# WL-DAC.net
KiCad netlist of a schematic drawn in Altium Designer
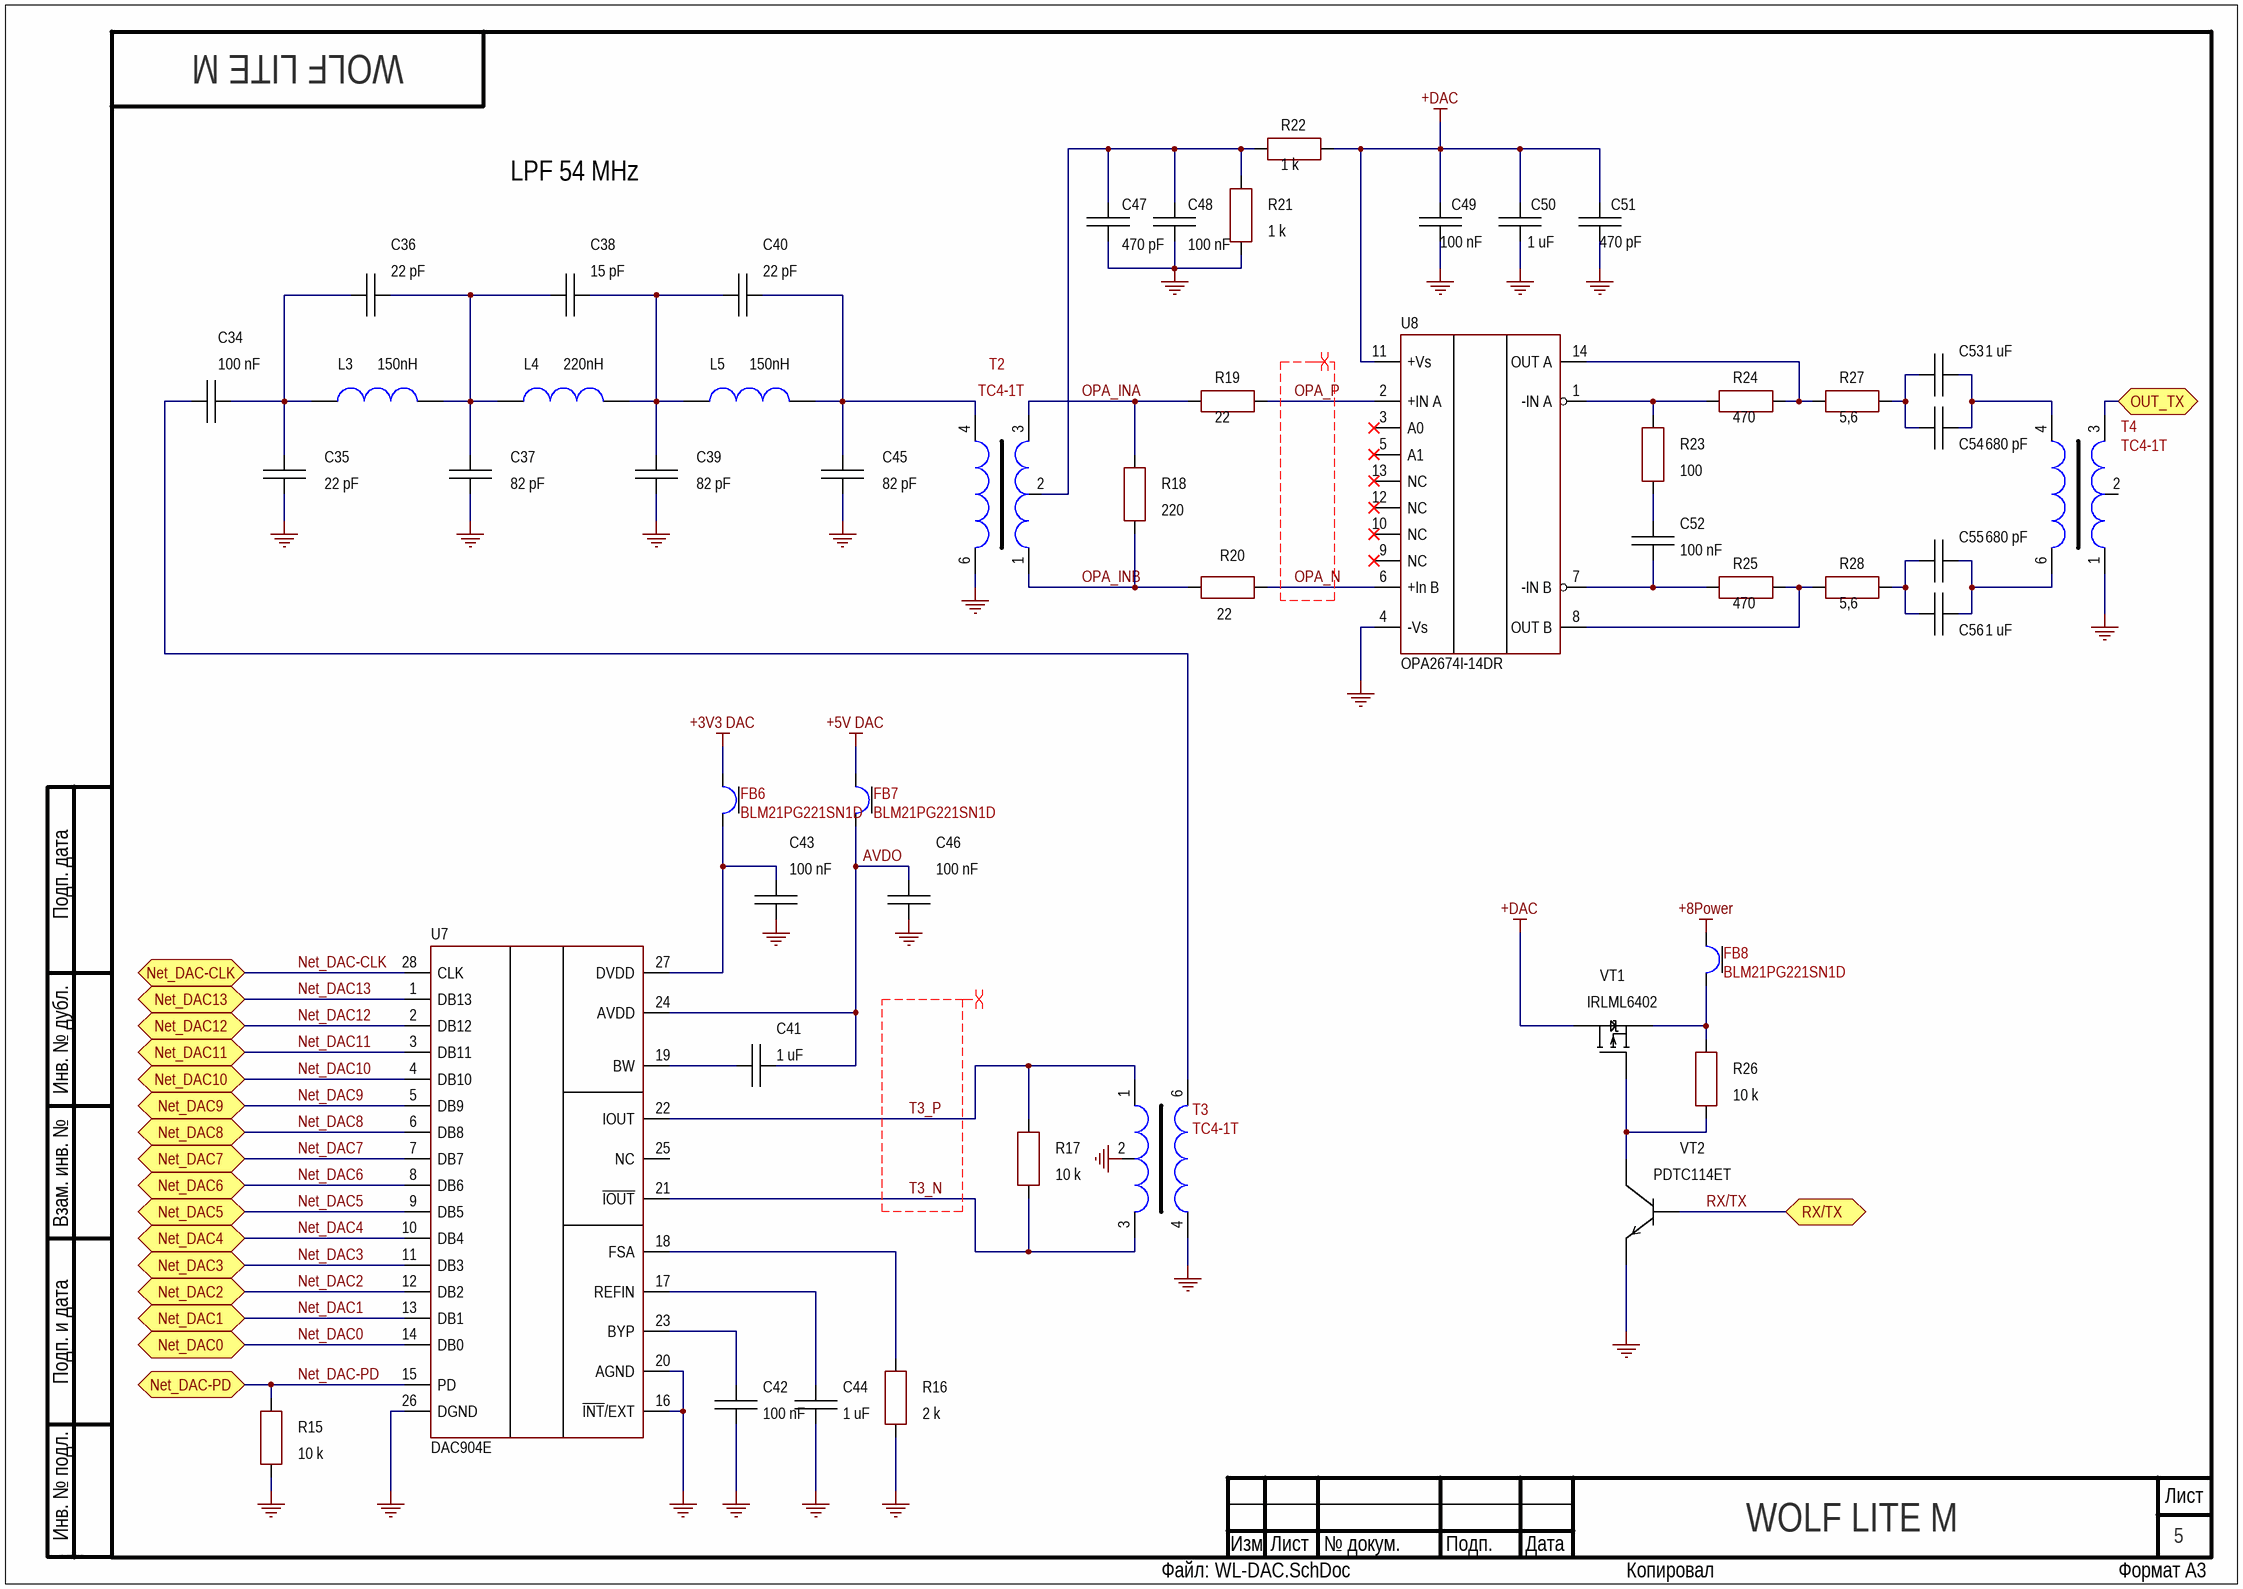
[diagram p0: WL-DAC.SchDoc]

(export (version "E")
  (design (tool "Eeschema 10.0.6"))
  (components
    (comp (ref "C34")
      (value "100 nF")
      (footprint "C-0805-0.95")
      (fields
        (field (name "MANUFACTURER") "Yageo")
        (field (name "PART NUMBER") "CC0805KRX7R9BB104")
        (field (name "TOLERANCE") "±10%")
      )
      (libsource (lib "GOST") (part "Capacitor"))
    )
    (comp (ref "C35")
      (value "22 pF")
      (footprint "C-0805-0.7")
      (fields
        (field (name "MANUFACTURER") "Yageo")
        (field (name "PART NUMBER") "CC0805JRNPO9BN220")
        (field (name "TOLERANCE") "±5%")
      )
      (libsource (lib "GOST") (part "Capacitor"))
    )
    (comp (ref "C36")
      (value "22 pF")
      (footprint "C-0805-0.7")
      (fields
        (field (name "MANUFACTURER") "Yageo")
        (field (name "PART NUMBER") "CC0805JRNPO9BN220")
        (field (name "TOLERANCE") "±5%")
      )
      (libsource (lib "GOST") (part "Capacitor"))
    )
    (comp (ref "C37")
      (value "82 pF")
      (footprint "C-0805-0.7")
      (fields
        (field (name "MANUFACTURER") "Yageo")
        (field (name "PART NUMBER") "CC0805JRNPO9BN820")
        (field (name "TOLERANCE") "±5%")
      )
      (libsource (lib "GOST") (part "Capacitor"))
    )
    (comp (ref "C38")
      (value "15 pF")
      (footprint "C-0805-0.7")
      (fields
        (field (name "MANUFACTURER") "Yageo")
        (field (name "PART NUMBER") "CC0805JRNPO9BN150")
        (field (name "TOLERANCE") "±5%")
      )
      (libsource (lib "GOST") (part "Capacitor"))
    )
    (comp (ref "C39")
      (value "82 pF")
      (footprint "C-0805-0.7")
      (fields
        (field (name "MANUFACTURER") "Yageo")
        (field (name "PART NUMBER") "CC0805JRNPO9BN820")
        (field (name "TOLERANCE") "±5%")
      )
      (libsource (lib "GOST") (part "Capacitor"))
    )
    (comp (ref "C40")
      (value "22 pF")
      (footprint "C-0805-0.7")
      (fields
        (field (name "MANUFACTURER") "Yageo")
        (field (name "PART NUMBER") "CC0805JRNPO9BN220")
        (field (name "TOLERANCE") "±5%")
      )
      (libsource (lib "GOST") (part "Capacitor"))
    )
    (comp (ref "C41")
      (value "1 uF")
      (footprint "C-0805-1.25")
      (fields
        (field (name "MANUFACTURER") "Yageo")
        (field (name "PART NUMBER") "CC0805KKX7R9BB105")
        (field (name "TOLERANCE") "±10%")
      )
      (libsource (lib "GOST") (part "Capacitor"))
    )
    (comp (ref "C42")
      (value "100 nF")
      (footprint "C-0805-0.95")
      (fields
        (field (name "MANUFACTURER") "Yageo")
        (field (name "PART NUMBER") "CC0805KRX7R9BB104")
        (field (name "TOLERANCE") "±10%")
      )
      (libsource (lib "GOST") (part "Capacitor"))
    )
    (comp (ref "C43")
      (value "100 nF")
      (footprint "C-0805-0.95")
      (fields
        (field (name "MANUFACTURER") "Yageo")
        (field (name "PART NUMBER") "CC0805KRX7R9BB104")
        (field (name "TOLERANCE") "±10%")
      )
      (libsource (lib "GOST") (part "Capacitor"))
    )
    (comp (ref "C44")
      (value "1 uF")
      (footprint "C-0805-1.25")
      (fields
        (field (name "MANUFACTURER") "Yageo")
        (field (name "PART NUMBER") "CC0805KKX7R9BB105")
        (field (name "TOLERANCE") "±10%")
      )
      (libsource (lib "GOST") (part "Capacitor"))
    )
    (comp (ref "C45")
      (value "82 pF")
      (footprint "C-0805-0.7")
      (fields
        (field (name "MANUFACTURER") "Yageo")
        (field (name "PART NUMBER") "CC0805JRNPO9BN820")
        (field (name "TOLERANCE") "±5%")
      )
      (libsource (lib "GOST") (part "Capacitor"))
    )
    (comp (ref "C46")
      (value "100 nF")
      (footprint "C-0805-0.95")
      (fields
        (field (name "MANUFACTURER") "Yageo")
        (field (name "PART NUMBER") "CC0805KRX7R9BB104")
        (field (name "TOLERANCE") "±10%")
      )
      (libsource (lib "GOST") (part "Capacitor"))
    )
    (comp (ref "C47")
      (value "470 pF")
      (footprint "C-0805-0.7")
      (fields
        (field (name "MANUFACTURER") "Yageo")
        (field (name "PART NUMBER") "CC0805JRNPO9BN471")
        (field (name "TOLERANCE") "±5%")
      )
      (libsource (lib "GOST") (part "Capacitor"))
    )
    (comp (ref "C48")
      (value "100 nF")
      (footprint "C-0805-0.95")
      (fields
        (field (name "MANUFACTURER") "Yageo")
        (field (name "PART NUMBER") "CC0805KRX7R9BB104")
        (field (name "TOLERANCE") "±10%")
      )
      (libsource (lib "GOST") (part "Capacitor"))
    )
    (comp (ref "C49")
      (value "100 nF")
      (footprint "C-0805-0.95")
      (fields
        (field (name "MANUFACTURER") "Yageo")
        (field (name "PART NUMBER") "CC0805KRX7R9BB104")
        (field (name "TOLERANCE") "±10%")
      )
      (libsource (lib "GOST") (part "Capacitor"))
    )
    (comp (ref "C50")
      (value "1 uF")
      (footprint "C-0805-1.25")
      (fields
        (field (name "MANUFACTURER") "Yageo")
        (field (name "PART NUMBER") "CC0805KKX7R9BB105")
        (field (name "TOLERANCE") "±10%")
      )
      (libsource (lib "GOST") (part "Capacitor"))
    )
    (comp (ref "C51")
      (value "470 pF")
      (footprint "C-0805-0.7")
      (fields
        (field (name "MANUFACTURER") "Yageo")
        (field (name "PART NUMBER") "CC0805JRNPO9BN471")
        (field (name "TOLERANCE") "±5%")
      )
      (libsource (lib "GOST") (part "Capacitor"))
    )
    (comp (ref "C52")
      (value "100 nF")
      (footprint "C-0805-0.95")
      (fields
        (field (name "MANUFACTURER") "Yageo")
        (field (name "PART NUMBER") "CC0805KRX7R9BB104")
        (field (name "TOLERANCE") "±10%")
      )
      (libsource (lib "GOST") (part "Capacitor"))
    )
    (comp (ref "C53")
      (value "1 uF")
      (footprint "C-0805-1.25")
      (fields
        (field (name "MANUFACTURER") "Yageo")
        (field (name "PART NUMBER") "CC0805KKX7R9BB105")
        (field (name "TOLERANCE") "±10%")
      )
      (libsource (lib "GOST") (part "Capacitor"))
    )
    (comp (ref "C54")
      (value "680 pF")
      (footprint "C-0805-0.7")
      (fields
        (field (name "MANUFACTURER") "Yageo")
        (field (name "PART NUMBER") "CC0805JRNPO9BN681")
        (field (name "TOLERANCE") "±5%")
      )
      (libsource (lib "GOST") (part "Capacitor"))
    )
    (comp (ref "C55")
      (value "680 pF")
      (footprint "C-0805-0.7")
      (fields
        (field (name "MANUFACTURER") "Yageo")
        (field (name "PART NUMBER") "CC0805JRNPO9BN681")
        (field (name "TOLERANCE") "±5%")
      )
      (libsource (lib "GOST") (part "Capacitor"))
    )
    (comp (ref "C56")
      (value "1 uF")
      (footprint "C-0805-1.25")
      (fields
        (field (name "MANUFACTURER") "Yageo")
        (field (name "PART NUMBER") "CC0805KKX7R9BB105")
        (field (name "TOLERANCE") "±10%")
      )
      (libsource (lib "GOST") (part "Capacitor"))
    )
    (comp (ref "FB6")
      (value "BLM21PG221SN1D")
      (footprint "L-0805")
      (fields (field (name "MANUFACTURER") "Murata Electronics"))
      (libsource (lib "GOST") (part "Ferrite Bead"))
    )
    (comp (ref "FB7")
      (value "BLM21PG221SN1D")
      (footprint "L-0805")
      (fields (field (name "MANUFACTURER") "Murata Electronics"))
      (libsource (lib "GOST") (part "Ferrite Bead"))
    )
    (comp (ref "FB8")
      (value "BLM21PG221SN1D")
      (footprint "L-0805")
      (fields (field (name "MANUFACTURER") "Murata Electronics"))
      (libsource (lib "GOST") (part "Ferrite Bead"))
    )
    (comp (ref "L3")
      (value "150nH")
      (footprint "L-1210")
      (fields
        (field (name "PART NUMBER") "FHW1210HCR15JGT")
        (field (name "MANUFACTURER") "FH(Guangdong Fenghua Advanced Tech)")
      )
      (libsource (lib "GOST") (part "Inductor"))
    )
    (comp (ref "L4")
      (value "220nH")
      (footprint "L-1210")
      (fields
        (field (name "PART NUMBER") "FHW1210HCR22JGT")
        (field (name "MANUFACTURER") "FH(Guangdong Fenghua Advanced Tech)")
      )
      (libsource (lib "GOST") (part "Inductor"))
    )
    (comp (ref "L5")
      (value "150nH")
      (footprint "L-1210")
      (fields
        (field (name "PART NUMBER") "FHW1210HCR15JGT")
        (field (name "MANUFACTURER") "FH(Guangdong Fenghua Advanced Tech)")
      )
      (libsource (lib "GOST") (part "Inductor"))
    )
    (comp (ref "R15")
      (value "10 k")
      (footprint "R-0805")
      (fields
        (field (name "MANUFACTURER") "Yageo")
        (field (name "PART NUMBER") "RC0805JR-0710KL")
        (field (name "POWER") "0,125 W")
      )
      (libsource (lib "") (part "Resistor_2"))
    )
    (comp (ref "R16")
      (value "2 k")
      (footprint "R-0805")
      (fields
        (field (name "MANUFACTURER") "Yageo")
        (field (name "PART NUMBER") "RC0805JR-072KL")
        (field (name "POWER") "0,125 W")
      )
      (libsource (lib "") (part "Resistor_2"))
    )
    (comp (ref "R17")
      (value "10 k")
      (footprint "R-0805")
      (fields
        (field (name "MANUFACTURER") "Yageo")
        (field (name "PART NUMBER") "RC0805JR-0710KL")
        (field (name "POWER") "0,125 W")
      )
      (libsource (lib "") (part "Resistor_1"))
    )
    (comp (ref "R18")
      (value "220")
      (footprint "R-0805")
      (fields
        (field (name "MANUFACTURER") "Yageo")
        (field (name "PART NUMBER") "RC0805JR-07220RL")
        (field (name "POWER") "0,125 W")
      )
      (libsource (lib "") (part "Resistor_1"))
    )
    (comp (ref "R19")
      (value "22")
      (footprint "R-0805")
      (fields
        (field (name "MANUFACTURER") "Yageo")
        (field (name "PART NUMBER") "RC0805JR-0722RL")
        (field (name "POWER") "0,125 W")
      )
      (libsource (lib "GOST") (part "Resistor"))
    )
    (comp (ref "R20")
      (value "22")
      (footprint "R-0805")
      (fields
        (field (name "MANUFACTURER") "Yageo")
        (field (name "PART NUMBER") "RC0805JR-0722RL")
        (field (name "POWER") "0,125 W")
      )
      (libsource (lib "GOST") (part "Resistor"))
    )
    (comp (ref "R21")
      (value "1 k")
      (footprint "R-0805")
      (fields
        (field (name "MANUFACTURER") "Yageo")
        (field (name "PART NUMBER") "RC0805JR-071KL")
        (field (name "POWER") "0,125 W")
      )
      (libsource (lib "") (part "Resistor_1"))
    )
    (comp (ref "R22")
      (value "1 k")
      (footprint "R-0805")
      (fields
        (field (name "MANUFACTURER") "Yageo")
        (field (name "PART NUMBER") "RC0805JR-071KL")
        (field (name "POWER") "0,125 W")
      )
      (libsource (lib "") (part "Resistor_1"))
    )
    (comp (ref "R23")
      (value "100")
      (footprint "R-0805")
      (fields
        (field (name "MANUFACTURER") "Yageo")
        (field (name "PART NUMBER") "RC0805JR-07100RL")
        (field (name "POWER") "0,125 W")
      )
      (libsource (lib "") (part "Resistor_2"))
    )
    (comp (ref "R24")
      (value "470")
      (footprint "R-0805")
      (fields
        (field (name "MANUFACTURER") "Yageo")
        (field (name "PART NUMBER") "RC0805JR-07470RL")
        (field (name "POWER") "0,125 W")
      )
      (libsource (lib "GOST") (part "Resistor"))
    )
    (comp (ref "R25")
      (value "470")
      (footprint "R-0805")
      (fields
        (field (name "MANUFACTURER") "Yageo")
        (field (name "PART NUMBER") "RC0805JR-07470RL")
        (field (name "POWER") "0,125 W")
      )
      (libsource (lib "GOST") (part "Resistor"))
    )
    (comp (ref "R26")
      (value "10 k")
      (footprint "R-0805")
      (fields
        (field (name "MANUFACTURER") "Yageo")
        (field (name "PART NUMBER") "RC0805JR-0710KL")
        (field (name "POWER") "0,125 W")
      )
      (libsource (lib "") (part "Resistor_2"))
    )
    (comp (ref "R27")
      (value "5,6")
      (footprint "R-0805")
      (fields
        (field (name "MANUFACTURER") "Yageo")
        (field (name "PART NUMBER") "RC0805JR-075R6L")
        (field (name "POWER") "0,125 W")
      )
      (libsource (lib "GOST") (part "Resistor"))
    )
    (comp (ref "R28")
      (value "5,6")
      (footprint "R-0805")
      (fields
        (field (name "MANUFACTURER") "Yageo")
        (field (name "PART NUMBER") "RC0805JR-075R6L")
        (field (name "POWER") "0,125 W")
      )
      (libsource (lib "GOST") (part "Resistor"))
    )
    (comp (ref "T2")
      (value "TC4-1T")
      (footprint "TC4-1T")
      (fields (field (name "MANUFACTURER") "Mini-Circuits"))
      (libsource (lib "GOST") (part "TC4-1T"))
    )
    (comp (ref "T3")
      (value "TC4-1T")
      (footprint "TC4-1T")
      (fields (field (name "MANUFACTURER") "Mini-Circuits"))
      (libsource (lib "GOST") (part "TC4-1T"))
    )
    (comp (ref "T4")
      (value "TC4-1T")
      (footprint "TC4-1T")
      (fields (field (name "MANUFACTURER") "Mini-Circuits"))
      (libsource (lib "GOST") (part "TC4-1T"))
    )
    (comp (ref "U7")
      (value "DAC904E")
      (footprint "TSSOP-28")
      (description "IC DAC 14BIT")
      (fields (field (name "MANUFACTURER") "Texas Instruments"))
      (libsource (lib "GOST") (part "DAC904E"))
    )
    (comp (ref "U8")
      (value "OPA2674I-14DR")
      (footprint "SOIC-14")
      (description "IC OPAMP CFA 2 CIRCUIT")
      (fields (field (name "MANUFACTURER") "Texas Instruments"))
      (libsource (lib "GOST") (part "OPA2674I-14DR"))
    )
    (comp (ref "VT1")
      (value "IRLML6402")
      (footprint "SOT-23")
      (fields
        (field (name "PART NUMBER") "IRLML6402TRPBF")
        (field (name "MANUFACTURER") "Infineon Technologies")
      )
      (libsource (lib "GOST") (part "MOSFET-P"))
    )
    (comp (ref "VT2")
      (value "PDTC114ET")
      (footprint "SOT-23")
      (fields (field (name "PART NUMBER") "PDTC114ET,215") (field (name "MANUFACTURER") "Nexperia USA Inc."))
      (libsource (lib "GOST") (part "BJT-NPN"))
    )
  )
  (nets
    (net (code "1") (name "+3V3 DAC") (class "Default")
      (node (ref "FB6") (pin "2") (pinfunction "2_2") (pintype "passive"))
    )
    (net (code "2") (name "+5V DAC") (class "Default")
      (node (ref "FB7") (pin "2") (pinfunction "2_2") (pintype "passive"))
    )
    (net (code "3") (name "+8Power") (class "Default")
      (node (ref "FB8") (pin "2") (pinfunction "2_2") (pintype "passive"))
    )
    (net (code "4") (name "+DAC") (class "Default")
      (node (ref "C49") (pin "1") (pinfunction "1_1") (pintype "passive"))
      (node (ref "C50") (pin "1") (pinfunction "1_1") (pintype "passive"))
      (node (ref "C51") (pin "1") (pinfunction "1_1") (pintype "passive"))
      (node (ref "R22") (pin "1") (pinfunction "1_1") (pintype "passive"))
      (node (ref "U8") (pin "11") (pinfunction "+Vs_11") (pintype "passive"))
      (node (ref "VT1") (pin "3") (pinfunction "D_3") (pintype "passive"))
    )
    (net (code "5") (name "/AVDO") (class "Default")
      (node (ref "C41") (pin "2") (pinfunction "2_2") (pintype "passive"))
      (node (ref "C46") (pin "1") (pinfunction "1_1") (pintype "passive"))
      (node (ref "FB7") (pin "1") (pinfunction "1_1") (pintype "passive"))
      (node (ref "U7") (pin "24") (pinfunction "AVDD_24") (pintype "passive"))
    )
    (net (code "6") (name "/Net_DAC-CLK") (class "Default")
      (node (ref "U7") (pin "28") (pinfunction "CLK_28") (pintype "passive"))
    )
    (net (code "7") (name "/Net_DAC-PD") (class "Default")
      (node (ref "R15") (pin "2") (pinfunction "2_2") (pintype "passive"))
      (node (ref "U7") (pin "15") (pinfunction "PD_15") (pintype "passive"))
    )
    (net (code "8") (name "/Net_DAC0") (class "Default")
      (node (ref "U7") (pin "14") (pinfunction "DB0_14") (pintype "passive"))
    )
    (net (code "9") (name "/Net_DAC1") (class "Default")
      (node (ref "U7") (pin "13") (pinfunction "DB1_13") (pintype "passive"))
    )
    (net (code "10") (name "/Net_DAC2") (class "Default")
      (node (ref "U7") (pin "12") (pinfunction "DB2_12") (pintype "passive"))
    )
    (net (code "11") (name "/Net_DAC3") (class "Default")
      (node (ref "U7") (pin "11") (pinfunction "DB3_11") (pintype "passive"))
    )
    (net (code "12") (name "/Net_DAC4") (class "Default")
      (node (ref "U7") (pin "10") (pinfunction "DB4_10") (pintype "passive"))
    )
    (net (code "13") (name "/Net_DAC5") (class "Default")
      (node (ref "U7") (pin "9") (pinfunction "DB5_9") (pintype "passive"))
    )
    (net (code "14") (name "/Net_DAC6") (class "Default")
      (node (ref "U7") (pin "8") (pinfunction "DB6_8") (pintype "passive"))
    )
    (net (code "15") (name "/Net_DAC7") (class "Default")
      (node (ref "U7") (pin "7") (pinfunction "DB7_7") (pintype "passive"))
    )
    (net (code "16") (name "/Net_DAC8") (class "Default")
      (node (ref "U7") (pin "6") (pinfunction "DB8_6") (pintype "passive"))
    )
    (net (code "17") (name "/Net_DAC9") (class "Default")
      (node (ref "U7") (pin "5") (pinfunction "DB9_5") (pintype "passive"))
    )
    (net (code "18") (name "/Net_DAC10") (class "Default")
      (node (ref "U7") (pin "4") (pinfunction "DB10_4") (pintype "passive"))
    )
    (net (code "19") (name "/Net_DAC11") (class "Default")
      (node (ref "U7") (pin "3") (pinfunction "DB11_3") (pintype "passive"))
    )
    (net (code "20") (name "/Net_DAC12") (class "Default")
      (node (ref "U7") (pin "2") (pinfunction "DB12_2") (pintype "passive"))
    )
    (net (code "21") (name "/Net_DAC13") (class "Default")
      (node (ref "U7") (pin "1") (pinfunction "DB13_1") (pintype "passive"))
    )
    (net (code "22") (name "/OPA_INA") (class "Default")
      (node (ref "R18") (pin "1") (pinfunction "1_1") (pintype "passive"))
      (node (ref "R19") (pin "1") (pinfunction "1_1") (pintype "passive"))
      (node (ref "T2") (pin "3") (pinfunction "3_3") (pintype "passive"))
    )
    (net (code "23") (name "/OPA_INB") (class "Default")
      (node (ref "R18") (pin "2") (pinfunction "2_2") (pintype "passive"))
      (node (ref "R20") (pin "1") (pinfunction "1_1") (pintype "passive"))
      (node (ref "T2") (pin "1") (pinfunction "1_1") (pintype "passive"))
    )
    (net (code "24") (name "/OPA_N") (class "Default")
      (node (ref "R20") (pin "2") (pinfunction "2_2") (pintype "passive"))
      (node (ref "U8") (pin "6") (pinfunction "+In_B_6") (pintype "passive"))
    )
    (net (code "25") (name "/OPA_P") (class "Default")
      (node (ref "R19") (pin "2") (pinfunction "2_2") (pintype "passive"))
      (node (ref "U8") (pin "2") (pinfunction "+IN_A_2") (pintype "passive"))
    )
    (net (code "26") (name "/OUT_TX") (class "Default")
      (node (ref "T4") (pin "3") (pinfunction "3_3") (pintype "passive"))
    )
    (net (code "27") (name "/RX{slash}TX") (class "Default")
      (node (ref "VT2") (pin "1") (pinfunction "1_1") (pintype "passive"))
    )
    (net (code "28") (name "/T3_N") (class "Default")
      (node (ref "R17") (pin "2") (pinfunction "2_2") (pintype "passive"))
      (node (ref "T3") (pin "3") (pinfunction "3_3") (pintype "passive"))
      (node (ref "U7") (pin "21") (pinfunction "IOUT_21") (pintype "passive"))
    )
    (net (code "29") (name "/T3_P") (class "Default")
      (node (ref "R17") (pin "1") (pinfunction "1_1") (pintype "passive"))
      (node (ref "T3") (pin "1") (pinfunction "1_1") (pintype "passive"))
      (node (ref "U7") (pin "22") (pinfunction "IOUT_22") (pintype "passive"))
    )
    (net (code "30") (name "GND") (class "Default")
      (node (ref "C35") (pin "1") (pinfunction "1_1") (pintype "passive"))
      (node (ref "C37") (pin "1") (pinfunction "1_1") (pintype "passive"))
      (node (ref "C39") (pin "1") (pinfunction "1_1") (pintype "passive"))
      (node (ref "C42") (pin "2") (pinfunction "2_2") (pintype "passive"))
      (node (ref "C43") (pin "2") (pinfunction "2_2") (pintype "passive"))
      (node (ref "C44") (pin "2") (pinfunction "2_2") (pintype "passive"))
      (node (ref "C45") (pin "1") (pinfunction "1_1") (pintype "passive"))
      (node (ref "C46") (pin "2") (pinfunction "2_2") (pintype "passive"))
      (node (ref "C47") (pin "1") (pinfunction "1_1") (pintype "passive"))
      (node (ref "C48") (pin "1") (pinfunction "1_1") (pintype "passive"))
      (node (ref "C49") (pin "2") (pinfunction "2_2") (pintype "passive"))
      (node (ref "C50") (pin "2") (pinfunction "2_2") (pintype "passive"))
      (node (ref "C51") (pin "2") (pinfunction "2_2") (pintype "passive"))
      (node (ref "R15") (pin "1") (pinfunction "1_1") (pintype "passive"))
      (node (ref "R16") (pin "1") (pinfunction "1_1") (pintype "passive"))
      (node (ref "R21") (pin "2") (pinfunction "2_2") (pintype "passive"))
      (node (ref "T2") (pin "6") (pinfunction "6_6") (pintype "passive"))
      (node (ref "T3") (pin "2") (pinfunction "2_2") (pintype "passive"))
      (node (ref "T3") (pin "4") (pinfunction "4_4") (pintype "passive"))
      (node (ref "T4") (pin "1") (pinfunction "1_1") (pintype "passive"))
      (node (ref "U7") (pin "16") (pinfunction "~{INT}/EXT_16") (pintype "passive"))
      (node (ref "U7") (pin "20") (pinfunction "AGND_20") (pintype "passive"))
      (node (ref "U7") (pin "26") (pinfunction "DGND_26") (pintype "passive"))
      (node (ref "U8") (pin "4") (pinfunction "-Vs_4") (pintype "passive"))
      (node (ref "VT2") (pin "2") (pinfunction "2_2") (pintype "passive"))
    )
    (net (code "31") (name "Net-(C34-Pad1)") (class "Default")
      (node (ref "C34") (pin "1") (pinfunction "1_1") (pintype "passive"))
      (node (ref "T3") (pin "6") (pinfunction "6_6") (pintype "passive"))
    )
    (net (code "32") (name "Net-(C34-Pad2)") (class "Default")
      (node (ref "C34") (pin "2") (pinfunction "2_2") (pintype "passive"))
      (node (ref "C35") (pin "2") (pinfunction "2_2") (pintype "passive"))
      (node (ref "C36") (pin "1") (pinfunction "1_1") (pintype "passive"))
      (node (ref "L3") (pin "1") (pinfunction "1_1") (pintype "passive"))
    )
    (net (code "33") (name "Net-(C36-Pad2)") (class "Default")
      (node (ref "C36") (pin "2") (pinfunction "2_2") (pintype "passive"))
      (node (ref "C37") (pin "2") (pinfunction "2_2") (pintype "passive"))
      (node (ref "C38") (pin "1") (pinfunction "1_1") (pintype "passive"))
      (node (ref "L3") (pin "2") (pinfunction "2_2") (pintype "passive"))
      (node (ref "L4") (pin "1") (pinfunction "1_1") (pintype "passive"))
    )
    (net (code "34") (name "Net-(C38-Pad2)") (class "Default")
      (node (ref "C38") (pin "2") (pinfunction "2_2") (pintype "passive"))
      (node (ref "C39") (pin "2") (pinfunction "2_2") (pintype "passive"))
      (node (ref "C40") (pin "1") (pinfunction "1_1") (pintype "passive"))
      (node (ref "L4") (pin "2") (pinfunction "2_2") (pintype "passive"))
      (node (ref "L5") (pin "1") (pinfunction "1_1") (pintype "passive"))
    )
    (net (code "35") (name "Net-(C40-Pad2)") (class "Default")
      (node (ref "C40") (pin "2") (pinfunction "2_2") (pintype "passive"))
      (node (ref "C45") (pin "2") (pinfunction "2_2") (pintype "passive"))
      (node (ref "L5") (pin "2") (pinfunction "2_2") (pintype "passive"))
      (node (ref "T2") (pin "4") (pinfunction "4_4") (pintype "passive"))
    )
    (net (code "36") (name "Net-(C47-Pad2)") (class "Default")
      (node (ref "C47") (pin "2") (pinfunction "2_2") (pintype "passive"))
      (node (ref "C48") (pin "2") (pinfunction "2_2") (pintype "passive"))
      (node (ref "R21") (pin "1") (pinfunction "1_1") (pintype "passive"))
      (node (ref "R22") (pin "2") (pinfunction "2_2") (pintype "passive"))
      (node (ref "T2") (pin "2") (pinfunction "2_2") (pintype "passive"))
    )
    (net (code "37") (name "Net-(C52-Pad1)") (class "Default")
      (node (ref "C52") (pin "1") (pinfunction "1_1") (pintype "passive"))
      (node (ref "R23") (pin "1") (pinfunction "1_1") (pintype "passive"))
    )
    (net (code "38") (name "Net-(C53-Pad1)") (class "Default")
      (node (ref "C53") (pin "1") (pinfunction "1_1") (pintype "passive"))
      (node (ref "C54") (pin "1") (pinfunction "1_1") (pintype "passive"))
      (node (ref "R27") (pin "2") (pinfunction "2_2") (pintype "passive"))
    )
    (net (code "39") (name "Net-(C53-Pad2)") (class "Default")
      (node (ref "C53") (pin "2") (pinfunction "2_2") (pintype "passive"))
      (node (ref "C54") (pin "2") (pinfunction "2_2") (pintype "passive"))
      (node (ref "T4") (pin "4") (pinfunction "4_4") (pintype "passive"))
    )
    (net (code "40") (name "Net-(C55-Pad1)") (class "Default")
      (node (ref "C55") (pin "1") (pinfunction "1_1") (pintype "passive"))
      (node (ref "C56") (pin "1") (pinfunction "1_1") (pintype "passive"))
      (node (ref "R28") (pin "2") (pinfunction "2_2") (pintype "passive"))
    )
    (net (code "41") (name "Net-(C55-Pad2)") (class "Default")
      (node (ref "C55") (pin "2") (pinfunction "2_2") (pintype "passive"))
      (node (ref "C56") (pin "2") (pinfunction "2_2") (pintype "passive"))
      (node (ref "T4") (pin "6") (pinfunction "6_6") (pintype "passive"))
    )
    (net (code "42") (name "Net-(U7-BW)") (class "Default")
      (node (ref "C41") (pin "1") (pinfunction "1_1") (pintype "passive"))
      (node (ref "U7") (pin "19") (pinfunction "BW_19") (pintype "passive"))
    )
    (net (code "43") (name "Net-(U7-BYP)") (class "Default")
      (node (ref "C42") (pin "1") (pinfunction "1_1") (pintype "passive"))
      (node (ref "U7") (pin "23") (pinfunction "BYP_23") (pintype "passive"))
    )
    (net (code "44") (name "Net-(U7-DVDD)") (class "Default")
      (node (ref "C43") (pin "1") (pinfunction "1_1") (pintype "passive"))
      (node (ref "FB6") (pin "1") (pinfunction "1_1") (pintype "passive"))
      (node (ref "U7") (pin "27") (pinfunction "DVDD_27") (pintype "passive"))
    )
    (net (code "45") (name "Net-(U7-FSA)") (class "Default")
      (node (ref "R16") (pin "2") (pinfunction "2_2") (pintype "passive"))
      (node (ref "U7") (pin "18") (pinfunction "FSA_18") (pintype "passive"))
    )
    (net (code "46") (name "Net-(U7-REFIN)") (class "Default")
      (node (ref "C44") (pin "1") (pinfunction "1_1") (pintype "passive"))
      (node (ref "U7") (pin "17") (pinfunction "REFIN_17") (pintype "passive"))
    )
    (net (code "47") (name "Net-(U8--IN_A)") (class "Default")
      (node (ref "R23") (pin "2") (pinfunction "2_2") (pintype "passive"))
      (node (ref "R24") (pin "1") (pinfunction "1_1") (pintype "passive"))
      (node (ref "U8") (pin "1") (pinfunction "-IN_A_1") (pintype "passive"))
    )
    (net (code "48") (name "Net-(U8--IN_B)") (class "Default")
      (node (ref "C52") (pin "2") (pinfunction "2_2") (pintype "passive"))
      (node (ref "R25") (pin "1") (pinfunction "1_1") (pintype "passive"))
      (node (ref "U8") (pin "7") (pinfunction "-IN_B_7") (pintype "passive"))
    )
    (net (code "49") (name "Net-(U8-OUT_A)") (class "Default")
      (node (ref "R24") (pin "2") (pinfunction "2_2") (pintype "passive"))
      (node (ref "R27") (pin "1") (pinfunction "1_1") (pintype "passive"))
      (node (ref "U8") (pin "14") (pinfunction "OUT_A_14") (pintype "passive"))
    )
    (net (code "50") (name "Net-(U8-OUT_B)") (class "Default")
      (node (ref "R25") (pin "2") (pinfunction "2_2") (pintype "passive"))
      (node (ref "R28") (pin "1") (pinfunction "1_1") (pintype "passive"))
      (node (ref "U8") (pin "8") (pinfunction "OUT_B_8") (pintype "passive"))
    )
    (net (code "51") (name "Net-(VT1-G)") (class "Default")
      (node (ref "R26") (pin "1") (pinfunction "1_1") (pintype "passive"))
      (node (ref "VT1") (pin "1") (pinfunction "G_1") (pintype "passive"))
      (node (ref "VT2") (pin "3") (pinfunction "3_3") (pintype "passive"))
    )
    (net (code "52") (name "Net-(VT1-S)") (class "Default")
      (node (ref "FB8") (pin "1") (pinfunction "1_1") (pintype "passive"))
      (node (ref "R26") (pin "2") (pinfunction "2_2") (pintype "passive"))
      (node (ref "VT1") (pin "2") (pinfunction "S_2") (pintype "passive"))
    )
    (net (code "53") (name "unconnected-(T4-Pad2)") (class "Default")
      (node (ref "T4") (pin "2") (pinfunction "2_2") (pintype "passive"))
    )
    (net (code "54") (name "unconnected-(U7-NC-Pad25)") (class "Default")
      (node (ref "U7") (pin "25") (pinfunction "NC_25") (pintype "passive"))
    )
    (net (code "55") (name "unconnected-(U8-A0-Pad3)") (class "Default")
      (node (ref "U8") (pin "3") (pinfunction "A0_3") (pintype "passive+no_connect"))
    )
    (net (code "56") (name "unconnected-(U8-A1-Pad5)") (class "Default")
      (node (ref "U8") (pin "5") (pinfunction "A1_5") (pintype "passive+no_connect"))
    )
    (net (code "57") (name "unconnected-(U8-NC-Pad9)") (class "Default")
      (node (ref "U8") (pin "9") (pinfunction "NC_9") (pintype "passive+no_connect"))
    )
    (net (code "58") (name "unconnected-(U8-NC-Pad10)") (class "Default")
      (node (ref "U8") (pin "10") (pinfunction "NC_10") (pintype "passive+no_connect"))
    )
    (net (code "59") (name "unconnected-(U8-NC-Pad12)") (class "Default")
      (node (ref "U8") (pin "12") (pinfunction "NC_12") (pintype "passive+no_connect"))
    )
    (net (code "60") (name "unconnected-(U8-NC-Pad13)") (class "Default")
      (node (ref "U8") (pin "13") (pinfunction "NC_13") (pintype "passive+no_connect"))
    )
  )
)
